# RPi_SPI_inputs_v04.net
KiCad netlist of a schematic drawn in EAGLE
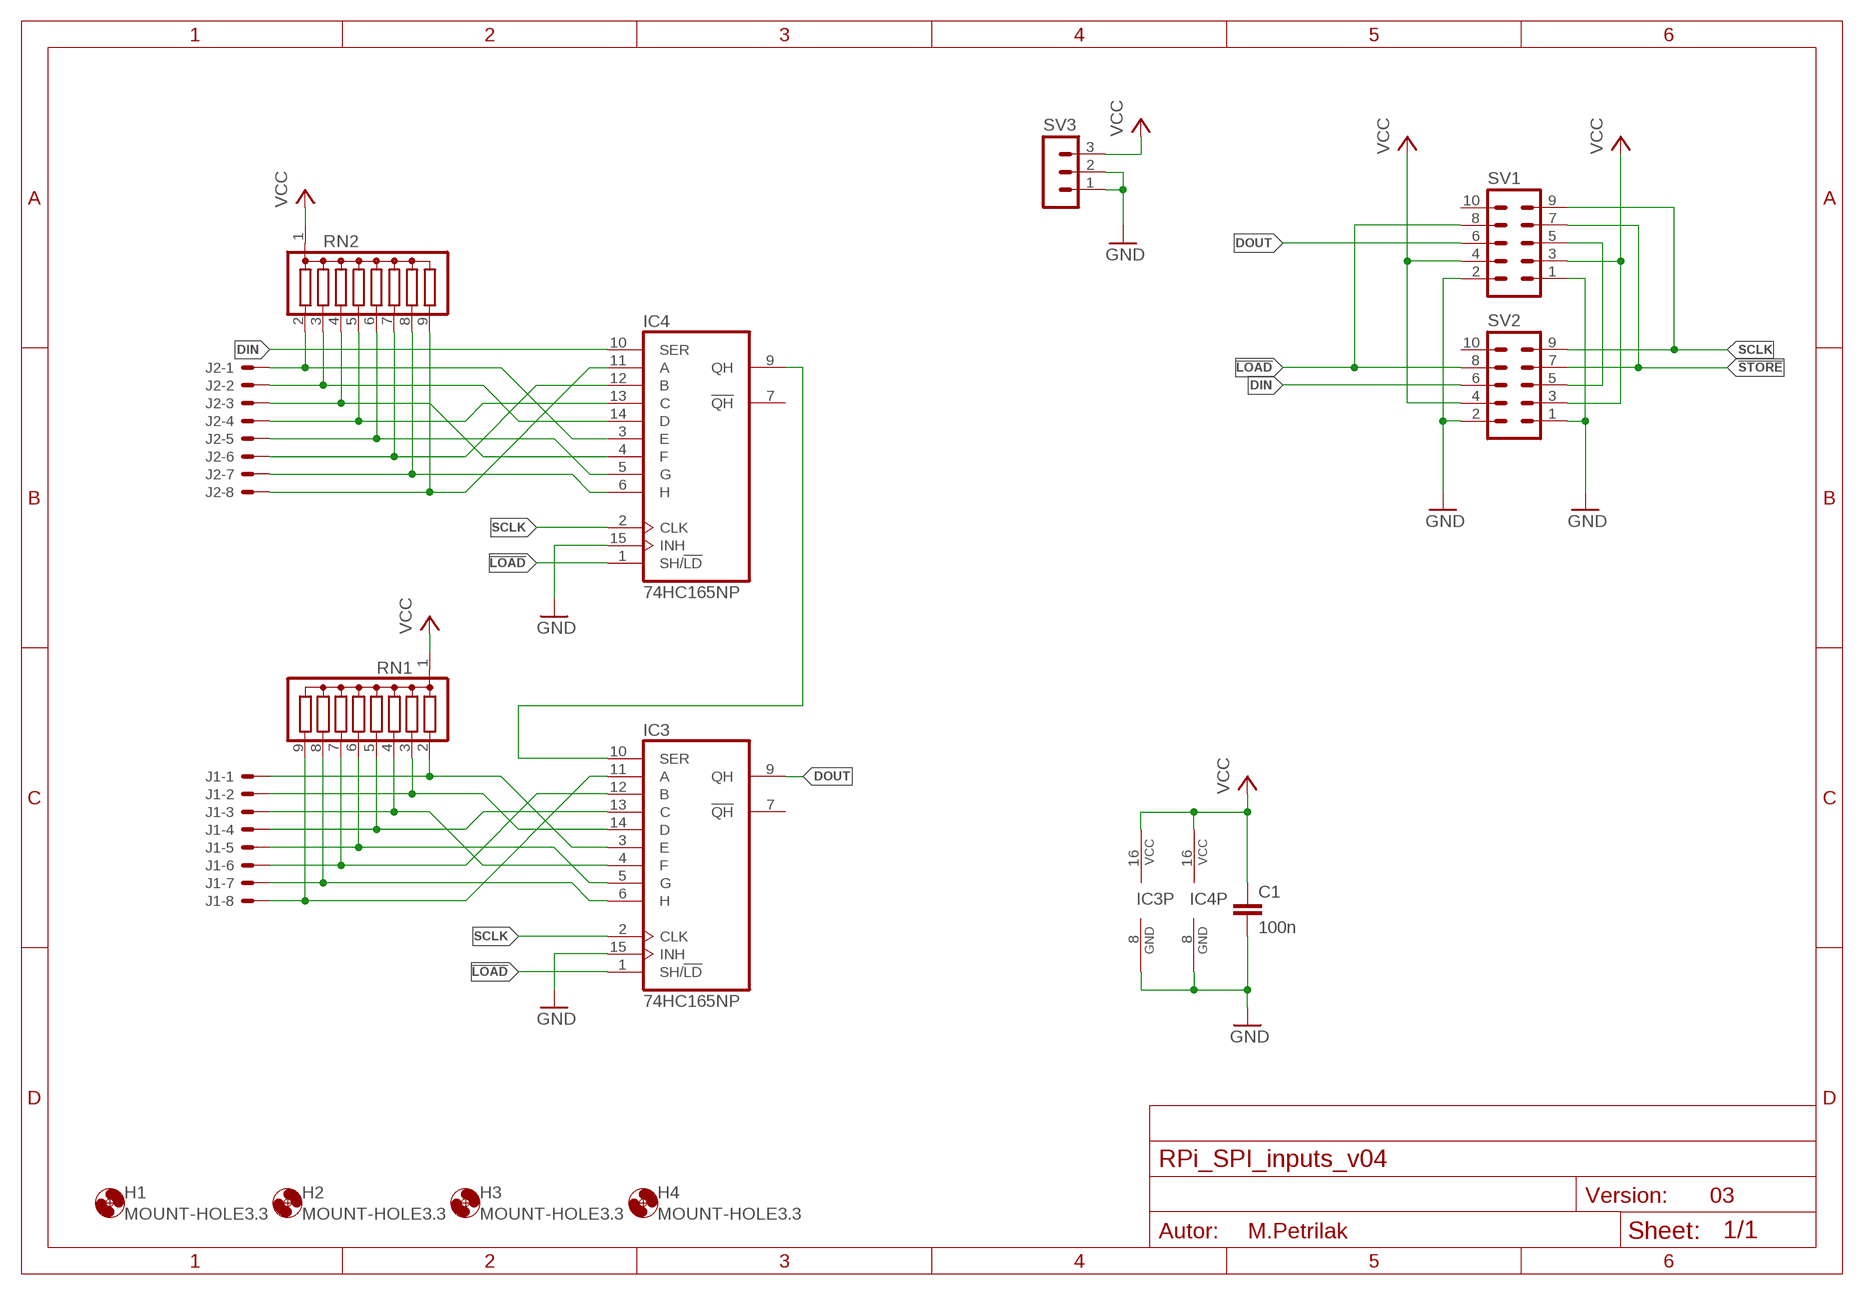
[diagram p0: schematic, sheet 1]

(export (version "E")
  (design (tool "Eeschema 10.0.6"))
  (components
    (comp (ref "C1")
      (value "100n")
      (footprint "eagle-import:C1206")
      (libsource (lib "eagle-import") (part "C-EUC1206"))
    )
    (comp (ref "H1")
      (value "MOUNT-HOLE3.3")
      (footprint "eagle-import:3,3")
      (libsource (lib "eagle-import") (part "MOUNT-HOLE3.3"))
    )
    (comp (ref "H2")
      (value "MOUNT-HOLE3.3")
      (footprint "eagle-import:3,3")
      (libsource (lib "eagle-import") (part "MOUNT-HOLE3.3"))
    )
    (comp (ref "H3")
      (value "MOUNT-HOLE3.3")
      (footprint "eagle-import:3,3")
      (libsource (lib "eagle-import") (part "MOUNT-HOLE3.3"))
    )
    (comp (ref "H4")
      (value "MOUNT-HOLE3.3")
      (footprint "eagle-import:3,3")
      (libsource (lib "eagle-import") (part "MOUNT-HOLE3.3"))
    )
    (comp (ref "IC3")
      (value "74HC165NP")
      (footprint "eagle-import:SOCKET-16")
      (libsource (lib "eagle-import") (part "74165NPHC"))
    )
    (comp (ref "IC4")
      (value "74HC165NP")
      (footprint "eagle-import:SOCKET-16")
      (libsource (lib "eagle-import") (part "74165NPHC"))
    )
    (comp (ref "J1")
      (value "22-05-7088-SPEC-08")
      (footprint "eagle-import:7395-08_SPEC")
      (libsource (lib "eagle-import") (part "22-?-0805-7088-SPEC"))
    )
    (comp (ref "J2")
      (value "22-05-7088-SPEC-08")
      (footprint "eagle-import:7395-08_SPEC")
      (libsource (lib "eagle-import") (part "22-?-0805-7088-SPEC"))
    )
    (comp (ref "RN1")
      (value "G08R")
      (footprint "eagle-import:SIL9")
      (libsource (lib "eagle-import") (part "G08R"))
    )
    (comp (ref "RN2")
      (value "G08R")
      (footprint "eagle-import:SIL9")
      (libsource (lib "eagle-import") (part "G08R"))
    )
    (comp (ref "SV1")
      (value "ML10")
      (footprint "eagle-import:ML10")
      (libsource (lib "eagle-import") (part "ML10"))
    )
    (comp (ref "SV2")
      (value "ML10")
      (footprint "eagle-import:ML10")
      (libsource (lib "eagle-import") (part "ML10"))
    )
    (comp (ref "SV3")
      (value "MA03-1_NO")
      (footprint "eagle-import:MA03-1_NO")
      (libsource (lib "eagle-import") (part "MA03-1_NO"))
    )
  )
  (nets
    (net (code "1") (name "/~{LOAD}") (class "Default")
      (node (ref "IC3") (pin "1") (pinfunction "SH/~{LD}_1") (pintype "input"))
      (node (ref "IC4") (pin "1") (pinfunction "SH/~{LD}_1") (pintype "input"))
      (node (ref "SV1") (pin "8") (pinfunction "8_8") (pintype "passive"))
      (node (ref "SV2") (pin "8") (pinfunction "8_8") (pintype "passive"))
    )
    (net (code "2") (name "/~{STORE}") (class "Default")
      (node (ref "SV1") (pin "7") (pinfunction "7_7") (pintype "passive"))
      (node (ref "SV2") (pin "7") (pinfunction "7_7") (pintype "passive"))
    )
    (net (code "3") (name "DIN") (class "Default")
      (node (ref "IC4") (pin "10") (pinfunction "SER_10") (pintype "input"))
      (node (ref "SV2") (pin "6") (pinfunction "6_6") (pintype "passive"))
    )
    (net (code "4") (name "DOUT") (class "Default")
      (node (ref "IC3") (pin "9") (pinfunction "QH_9") (pintype "output"))
      (node (ref "SV1") (pin "6") (pinfunction "6_6") (pintype "passive"))
    )
    (net (code "5") (name "GND") (class "Default")
      (node (ref "C1") (pin "2") (pinfunction "2_2") (pintype "passive"))
      (node (ref "IC3") (pin "15") (pinfunction "INH_15") (pintype "input"))
      (node (ref "IC3") (pin "8") (pinfunction "GND_8") (pintype "power_in"))
      (node (ref "IC4") (pin "15") (pinfunction "INH_15") (pintype "input"))
      (node (ref "IC4") (pin "8") (pinfunction "GND_8") (pintype "power_in"))
      (node (ref "SV1") (pin "1") (pinfunction "1_1") (pintype "passive"))
      (node (ref "SV1") (pin "2") (pinfunction "2_2") (pintype "passive"))
      (node (ref "SV2") (pin "1") (pinfunction "1_1") (pintype "passive"))
      (node (ref "SV2") (pin "2") (pinfunction "2_2") (pintype "passive"))
      (node (ref "SV3") (pin "1") (pinfunction "1_1") (pintype "passive"))
      (node (ref "SV3") (pin "2") (pinfunction "2_2") (pintype "passive"))
    )
    (net (code "6") (name "Net-(IC3A-A)") (class "Default")
      (node (ref "IC3") (pin "11") (pinfunction "A_11") (pintype "input"))
      (node (ref "J1") (pin "8") (pinfunction "S_8") (pintype "passive"))
      (node (ref "RN1") (pin "9") (pinfunction "9_9") (pintype "passive"))
    )
    (net (code "7") (name "Net-(IC3A-B)") (class "Default")
      (node (ref "IC3") (pin "12") (pinfunction "B_12") (pintype "input"))
      (node (ref "J1") (pin "6") (pinfunction "S_6") (pintype "passive"))
      (node (ref "RN1") (pin "7") (pinfunction "7_7") (pintype "passive"))
    )
    (net (code "8") (name "Net-(IC3A-C)") (class "Default")
      (node (ref "IC3") (pin "13") (pinfunction "C_13") (pintype "input"))
      (node (ref "J1") (pin "4") (pinfunction "S_4") (pintype "passive"))
      (node (ref "RN1") (pin "5") (pinfunction "5_5") (pintype "passive"))
    )
    (net (code "9") (name "Net-(IC3A-D)") (class "Default")
      (node (ref "IC3") (pin "14") (pinfunction "D_14") (pintype "input"))
      (node (ref "J1") (pin "2") (pinfunction "S_2") (pintype "passive"))
      (node (ref "RN1") (pin "3") (pinfunction "3_3") (pintype "passive"))
    )
    (net (code "10") (name "Net-(IC3A-E)") (class "Default")
      (node (ref "IC3") (pin "3") (pinfunction "E_3") (pintype "input"))
      (node (ref "J1") (pin "1") (pinfunction "S_1") (pintype "passive"))
      (node (ref "RN1") (pin "2") (pinfunction "2_2") (pintype "passive"))
    )
    (net (code "11") (name "Net-(IC3A-F)") (class "Default")
      (node (ref "IC3") (pin "4") (pinfunction "F_4") (pintype "input"))
      (node (ref "J1") (pin "3") (pinfunction "S_3") (pintype "passive"))
      (node (ref "RN1") (pin "4") (pinfunction "4_4") (pintype "passive"))
    )
    (net (code "12") (name "Net-(IC3A-G)") (class "Default")
      (node (ref "IC3") (pin "5") (pinfunction "G_5") (pintype "input"))
      (node (ref "J1") (pin "5") (pinfunction "S_5") (pintype "passive"))
      (node (ref "RN1") (pin "6") (pinfunction "6_6") (pintype "passive"))
    )
    (net (code "13") (name "Net-(IC3A-H)") (class "Default")
      (node (ref "IC3") (pin "6") (pinfunction "H_6") (pintype "input"))
      (node (ref "J1") (pin "7") (pinfunction "S_7") (pintype "passive"))
      (node (ref "RN1") (pin "8") (pinfunction "8_8") (pintype "passive"))
    )
    (net (code "14") (name "Net-(IC3A-SER)") (class "Default")
      (node (ref "IC3") (pin "10") (pinfunction "SER_10") (pintype "input"))
      (node (ref "IC4") (pin "9") (pinfunction "QH_9") (pintype "output"))
    )
    (net (code "15") (name "Net-(IC4A-A)") (class "Default")
      (node (ref "IC4") (pin "11") (pinfunction "A_11") (pintype "input"))
      (node (ref "J2") (pin "8") (pinfunction "S_8") (pintype "passive"))
      (node (ref "RN2") (pin "9") (pinfunction "9_9") (pintype "passive"))
    )
    (net (code "16") (name "Net-(IC4A-B)") (class "Default")
      (node (ref "IC4") (pin "12") (pinfunction "B_12") (pintype "input"))
      (node (ref "J2") (pin "6") (pinfunction "S_6") (pintype "passive"))
      (node (ref "RN2") (pin "7") (pinfunction "7_7") (pintype "passive"))
    )
    (net (code "17") (name "Net-(IC4A-C)") (class "Default")
      (node (ref "IC4") (pin "13") (pinfunction "C_13") (pintype "input"))
      (node (ref "J2") (pin "4") (pinfunction "S_4") (pintype "passive"))
      (node (ref "RN2") (pin "5") (pinfunction "5_5") (pintype "passive"))
    )
    (net (code "18") (name "Net-(IC4A-D)") (class "Default")
      (node (ref "IC4") (pin "14") (pinfunction "D_14") (pintype "input"))
      (node (ref "J2") (pin "2") (pinfunction "S_2") (pintype "passive"))
      (node (ref "RN2") (pin "3") (pinfunction "3_3") (pintype "passive"))
    )
    (net (code "19") (name "Net-(IC4A-E)") (class "Default")
      (node (ref "IC4") (pin "3") (pinfunction "E_3") (pintype "input"))
      (node (ref "J2") (pin "1") (pinfunction "S_1") (pintype "passive"))
      (node (ref "RN2") (pin "2") (pinfunction "2_2") (pintype "passive"))
    )
    (net (code "20") (name "Net-(IC4A-F)") (class "Default")
      (node (ref "IC4") (pin "4") (pinfunction "F_4") (pintype "input"))
      (node (ref "J2") (pin "3") (pinfunction "S_3") (pintype "passive"))
      (node (ref "RN2") (pin "4") (pinfunction "4_4") (pintype "passive"))
    )
    (net (code "21") (name "Net-(IC4A-G)") (class "Default")
      (node (ref "IC4") (pin "5") (pinfunction "G_5") (pintype "input"))
      (node (ref "J2") (pin "5") (pinfunction "S_5") (pintype "passive"))
      (node (ref "RN2") (pin "6") (pinfunction "6_6") (pintype "passive"))
    )
    (net (code "22") (name "Net-(IC4A-H)") (class "Default")
      (node (ref "IC4") (pin "6") (pinfunction "H_6") (pintype "input"))
      (node (ref "J2") (pin "7") (pinfunction "S_7") (pintype "passive"))
      (node (ref "RN2") (pin "8") (pinfunction "8_8") (pintype "passive"))
    )
    (net (code "23") (name "Net-(SV1-Pad5)") (class "Default")
      (node (ref "SV1") (pin "5") (pinfunction "5_5") (pintype "passive"))
      (node (ref "SV2") (pin "5") (pinfunction "5_5") (pintype "passive"))
    )
    (net (code "24") (name "SCLK") (class "Default")
      (node (ref "IC3") (pin "2") (pinfunction "CLK_2") (pintype "input"))
      (node (ref "IC4") (pin "2") (pinfunction "CLK_2") (pintype "input"))
      (node (ref "SV1") (pin "9") (pinfunction "9_9") (pintype "passive"))
      (node (ref "SV2") (pin "9") (pinfunction "9_9") (pintype "passive"))
    )
    (net (code "25") (name "VCC") (class "Default")
      (node (ref "C1") (pin "1") (pinfunction "1_1") (pintype "passive"))
      (node (ref "IC3") (pin "16") (pinfunction "VCC_16") (pintype "power_in"))
      (node (ref "IC4") (pin "16") (pinfunction "VCC_16") (pintype "power_in"))
      (node (ref "RN1") (pin "1") (pinfunction "1_1") (pintype "passive"))
      (node (ref "RN2") (pin "1") (pinfunction "1_1") (pintype "passive"))
      (node (ref "SV1") (pin "3") (pinfunction "3_3") (pintype "passive"))
      (node (ref "SV1") (pin "4") (pinfunction "4_4") (pintype "passive"))
      (node (ref "SV2") (pin "3") (pinfunction "3_3") (pintype "passive"))
      (node (ref "SV2") (pin "4") (pinfunction "4_4") (pintype "passive"))
      (node (ref "SV3") (pin "3") (pinfunction "3_3") (pintype "passive"))
    )
    (net (code "26") (name "unconnected-(IC3A-~{QH}-Pad7)") (class "Default")
      (node (ref "IC3") (pin "7") (pinfunction "~{QH}_7") (pintype "output"))
    )
    (net (code "27") (name "unconnected-(IC4A-~{QH}-Pad7)") (class "Default")
      (node (ref "IC4") (pin "7") (pinfunction "~{QH}_7") (pintype "output"))
    )
    (net (code "28") (name "unconnected-(SV1-Pad10)") (class "Default")
      (node (ref "SV1") (pin "10") (pinfunction "10_10") (pintype "passive"))
    )
    (net (code "29") (name "unconnected-(SV2-Pad10)") (class "Default")
      (node (ref "SV2") (pin "10") (pinfunction "10_10") (pintype "passive"))
    )
  )
)
